# 1206_1210.net
KiCad netlist of a schematic drawn in EAGLE
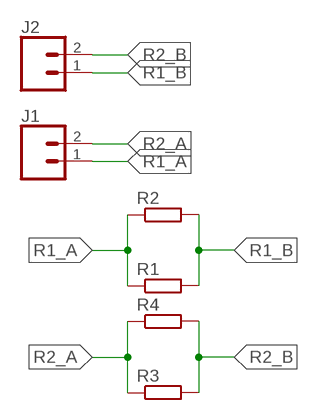
[diagram p0: schematic, sheet 1]

(export (version "E")
  (design (tool "Eeschema 10.0.6"))
  (components
    (comp (ref "J1")
      (value "CONN_02")
      (footprint "eagle-import:1X02")
      (libsource (lib "eagle-import") (part "CONN_02"))
    )
    (comp (ref "J2")
      (value "CONN_02")
      (footprint "eagle-import:1X02")
      (libsource (lib "eagle-import") (part "CONN_02"))
    )
    (comp (ref "R1")
      (value "R-EU_R1210")
      (footprint "eagle-import:R1210")
      (libsource (lib "eagle-import") (part "R-EU_R1210"))
    )
    (comp (ref "R2")
      (value "R-EU_R1206")
      (footprint "eagle-import:R1206")
      (libsource (lib "eagle-import") (part "R-EU_R1206"))
    )
    (comp (ref "R3")
      (value "R-EU_R1210")
      (footprint "eagle-import:R1210")
      (libsource (lib "eagle-import") (part "R-EU_R1210"))
    )
    (comp (ref "R4")
      (value "R-EU_R1206")
      (footprint "eagle-import:R1206")
      (libsource (lib "eagle-import") (part "R-EU_R1206"))
    )
  )
  (nets
    (net (code "1") (name "R1_A") (class "Default")
      (node (ref "J1") (pin "1") (pinfunction "1_1") (pintype "passive"))
      (node (ref "R1") (pin "1") (pinfunction "1_1") (pintype "passive"))
      (node (ref "R2") (pin "1") (pinfunction "1_1") (pintype "passive"))
    )
    (net (code "2") (name "R1_B") (class "Default")
      (node (ref "J2") (pin "1") (pinfunction "1_1") (pintype "passive"))
      (node (ref "R1") (pin "2") (pinfunction "2_2") (pintype "passive"))
      (node (ref "R2") (pin "2") (pinfunction "2_2") (pintype "passive"))
    )
    (net (code "3") (name "R2_A") (class "Default")
      (node (ref "J1") (pin "2") (pinfunction "2_2") (pintype "passive"))
      (node (ref "R3") (pin "1") (pinfunction "1_1") (pintype "passive"))
      (node (ref "R4") (pin "1") (pinfunction "1_1") (pintype "passive"))
    )
    (net (code "4") (name "R2_B") (class "Default")
      (node (ref "J2") (pin "2") (pinfunction "2_2") (pintype "passive"))
      (node (ref "R3") (pin "2") (pinfunction "2_2") (pintype "passive"))
      (node (ref "R4") (pin "2") (pinfunction "2_2") (pintype "passive"))
    )
  )
)
